# BattMon.net
KiCad netlist of a schematic drawn in EAGLE
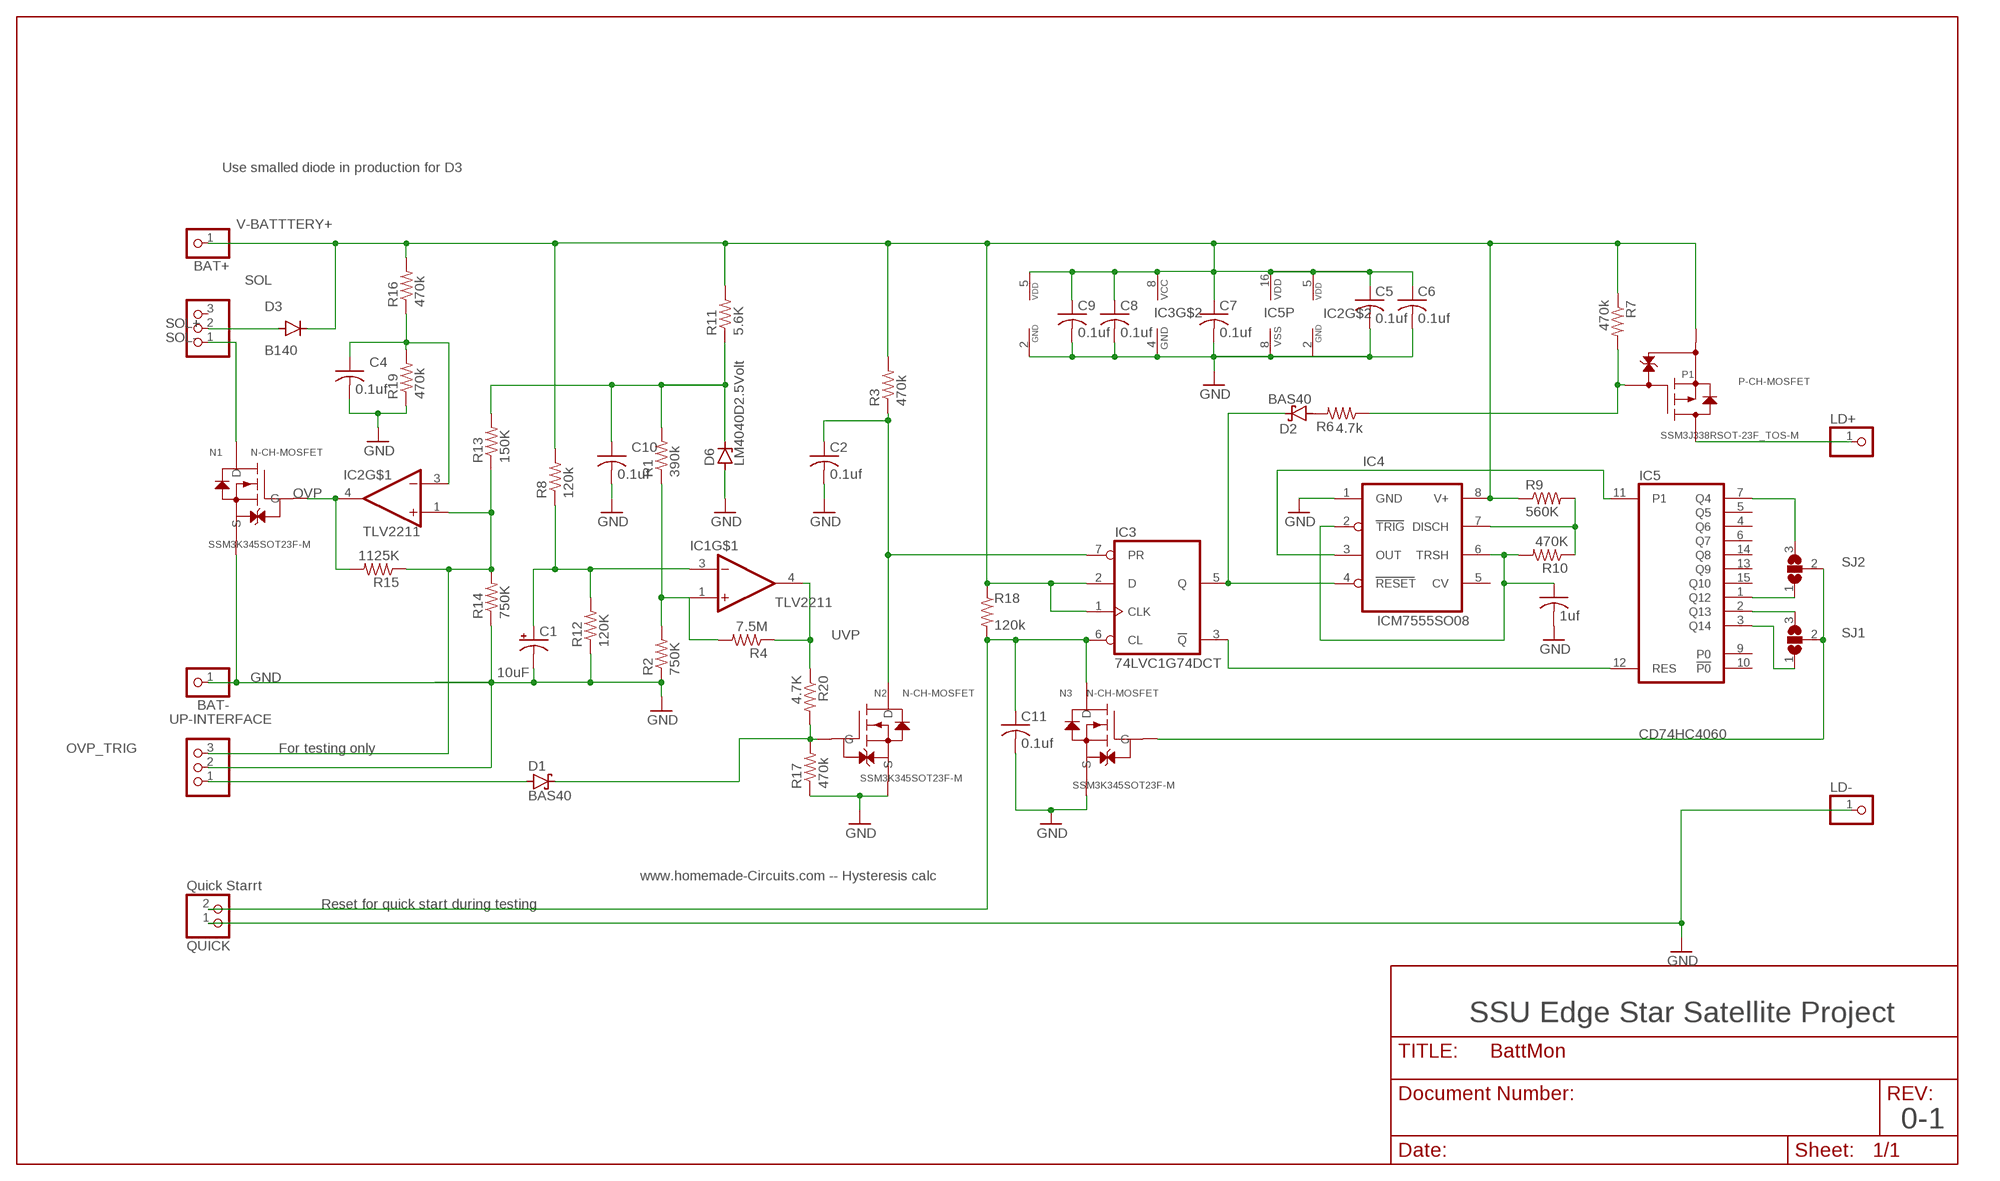
[diagram p0: schematic, sheet 1]

(export (version "E")
  (design (tool "Eeschema 10.0.6"))
  (components
    (comp (ref "BAT+")
      (value "PINHD-1X1")
      (footprint "eagle-import:1X01")
      (libsource (lib "eagle-import") (part "PINHD-1X1"))
    )
    (comp (ref "BAT-")
      (value "PINHD-1X1")
      (footprint "eagle-import:1X01")
      (libsource (lib "eagle-import") (part "PINHD-1X1"))
    )
    (comp (ref "C1")
      (value "10uF")
      (footprint "eagle-import:E2,5-6E")
      (libsource (lib "eagle-import") (part "CPOL-USE2,5-6E"))
    )
    (comp (ref "C2")
      (value "0.1uf")
      (footprint "eagle-import:C0805")
      (libsource (lib "eagle-import") (part "C-USC0805"))
    )
    (comp (ref "C3")
      (value "1uf")
      (footprint "eagle-import:C0805")
      (libsource (lib "eagle-import") (part "C-USC0805"))
    )
    (comp (ref "C4")
      (value "0.1uf")
      (footprint "eagle-import:C0805")
      (libsource (lib "eagle-import") (part "C-USC0805"))
    )
    (comp (ref "C5")
      (value "0.1uf")
      (footprint "eagle-import:C0805")
      (libsource (lib "eagle-import") (part "C-USC0805"))
    )
    (comp (ref "C6")
      (value "0.1uf")
      (footprint "eagle-import:C0805")
      (libsource (lib "eagle-import") (part "C-USC0805"))
    )
    (comp (ref "C7")
      (value "0.1uf")
      (footprint "eagle-import:C0805")
      (libsource (lib "eagle-import") (part "C-USC0805"))
    )
    (comp (ref "C8")
      (value "0.1uf")
      (footprint "eagle-import:C0805")
      (libsource (lib "eagle-import") (part "C-USC0805"))
    )
    (comp (ref "C9")
      (value "0.1uf")
      (footprint "eagle-import:C0805")
      (libsource (lib "eagle-import") (part "C-USC0805"))
    )
    (comp (ref "C10")
      (value "0.1uf")
      (footprint "eagle-import:C0805")
      (libsource (lib "eagle-import") (part "C-USC0805"))
    )
    (comp (ref "C11")
      (value "0.1uf")
      (footprint "eagle-import:C0805")
      (libsource (lib "eagle-import") (part "C-USC0805"))
    )
    (comp (ref "D1")
      (value "BAS40")
      (footprint "eagle-import:SOT23")
      (libsource (lib "eagle-import") (part "BAS40"))
    )
    (comp (ref "D2")
      (value "BAS40")
      (footprint "eagle-import:SOT23")
      (libsource (lib "eagle-import") (part "BAS40"))
    )
    (comp (ref "D3")
      (value "B140")
      (footprint "eagle-import:SMA")
      (libsource (lib "eagle-import") (part "S1M"))
    )
    (comp (ref "D6")
      (value "LM4040D2.5Volt")
      (footprint "eagle-import:SOT23")
      (libsource (lib "eagle-import") (part "LM4040"))
    )
    (comp (ref "IC1")
      (value "TLV2211")
      (footprint "eagle-import:SOT23-5")
      (libsource (lib "eagle-import") (part "TLVB2211"))
    )
    (comp (ref "IC2")
      (value "TLV2211")
      (footprint "eagle-import:SOT23-5")
      (fields (field (name "DIGIKEY") "296-10500-1-ND"))
      (libsource (lib "eagle-import") (part "TLVB2211"))
    )
    (comp (ref "IC3")
      (value "74LVC1G74DCT")
      (footprint "eagle-import:DCT_R-PDSO-G8")
      (fields (field (name "DIGIKEY") "SN74LVC1G74DCTR"))
      (libsource (lib "eagle-import") (part "741G74DCTLVC"))
    )
    (comp (ref "IC4")
      (value "ICM7555SO08")
      (footprint "eagle-import:SO08")
      (libsource (lib "eagle-import") (part "ICM7555SO08"))
    )
    (comp (ref "IC5")
      (value "CD74HC4060")
      (footprint "eagle-import:SO16")
      (fields (field (name "DIGIKEY") "296-25999-1-ND"))
      (libsource (lib "eagle-import") (part "4060D"))
    )
    (comp (ref "LD+")
      (value "PINHD-1X1")
      (footprint "eagle-import:1X01")
      (libsource (lib "eagle-import") (part "PINHD-1X1"))
    )
    (comp (ref "LD-")
      (value "PINHD-1X1")
      (footprint "eagle-import:1X01")
      (libsource (lib "eagle-import") (part "PINHD-1X1"))
    )
    (comp (ref "N1")
      (value "SSM3K345SOT23F-M")
      (footprint "eagle-import:SOT-23F_TOS-M")
      (libsource (lib "eagle-import") (part "SSM3K345SOT23F-M"))
    )
    (comp (ref "N2")
      (value "SSM3K345SOT23F-M")
      (footprint "eagle-import:SOT-23F_TOS-M")
      (libsource (lib "eagle-import") (part "SSM3K345SOT23F-M"))
    )
    (comp (ref "N3")
      (value "SSM3K345SOT23F-M")
      (footprint "eagle-import:SOT-23F_TOS-M")
      (libsource (lib "eagle-import") (part "SSM3K345SOT23F-M"))
    )
    (comp (ref "P1")
      (value "SSM3J338RSOT-23F_TOS-M")
      (footprint "eagle-import:SOT-23F_TOS-M")
      (fields (field (name "MANUFACTURER_PART_NUMBER") "SSM3J338R"))
      (libsource (lib "eagle-import") (part "SSM3J338RSOT-23F_TOS-M"))
    )
    (comp (ref "QUICK")
      (value "Quick Starrt")
      (footprint "eagle-import:1X02")
      (libsource (lib "eagle-import") (part "PINHD-1X2"))
    )
    (comp (ref "R1")
      (value "390k")
      (footprint "eagle-import:R0805")
      (libsource (lib "eagle-import") (part "R-US_R0805"))
    )
    (comp (ref "R2")
      (value "750K")
      (footprint "eagle-import:R0805")
      (libsource (lib "eagle-import") (part "R-US_R0805"))
    )
    (comp (ref "R3")
      (value "470k")
      (footprint "eagle-import:R0805")
      (libsource (lib "eagle-import") (part "R-US_R0805"))
    )
    (comp (ref "R4")
      (value "7.5M")
      (footprint "eagle-import:R0805")
      (libsource (lib "eagle-import") (part "R-US_R0805"))
    )
    (comp (ref "R6")
      (value "4.7k")
      (footprint "eagle-import:R0805")
      (libsource (lib "eagle-import") (part "R-US_R0805"))
    )
    (comp (ref "R7")
      (value "470k")
      (footprint "eagle-import:R0805")
      (libsource (lib "eagle-import") (part "R-US_R0805"))
    )
    (comp (ref "R8")
      (value "120k")
      (footprint "eagle-import:R0805")
      (libsource (lib "eagle-import") (part "R-US_R0805"))
    )
    (comp (ref "R9")
      (value "560K")
      (footprint "eagle-import:R0805")
      (libsource (lib "eagle-import") (part "R-US_R0805"))
    )
    (comp (ref "R10")
      (value "470K")
      (footprint "eagle-import:R0805")
      (libsource (lib "eagle-import") (part "R-US_R0805"))
    )
    (comp (ref "R11")
      (value "5.6K")
      (footprint "eagle-import:R0805")
      (libsource (lib "eagle-import") (part "R-US_R0805"))
    )
    (comp (ref "R12")
      (value "120K")
      (footprint "eagle-import:R0805")
      (libsource (lib "eagle-import") (part "R-US_R0805"))
    )
    (comp (ref "R13")
      (value "150K")
      (footprint "eagle-import:R0805")
      (libsource (lib "eagle-import") (part "R-US_R0805"))
    )
    (comp (ref "R14")
      (value "750K")
      (footprint "eagle-import:R0805")
      (libsource (lib "eagle-import") (part "R-US_R0805"))
    )
    (comp (ref "R15")
      (value "1125K")
      (footprint "eagle-import:R0805")
      (libsource (lib "eagle-import") (part "R-US_R0805"))
    )
    (comp (ref "R16")
      (value "470k")
      (footprint "eagle-import:R0805")
      (libsource (lib "eagle-import") (part "R-US_R0805"))
    )
    (comp (ref "R17")
      (value "470k")
      (footprint "eagle-import:R0805")
      (libsource (lib "eagle-import") (part "R-US_R0805"))
    )
    (comp (ref "R18")
      (value "120k")
      (footprint "eagle-import:R0805")
      (libsource (lib "eagle-import") (part "R-US_R0805"))
    )
    (comp (ref "R19")
      (value "470k")
      (footprint "eagle-import:R0805")
      (libsource (lib "eagle-import") (part "R-US_R0805"))
    )
    (comp (ref "R20")
      (value "4.7K")
      (footprint "eagle-import:R0805")
      (libsource (lib "eagle-import") (part "R-US_R0805"))
    )
    (comp (ref "SJ1")
      (value "SJ2W")
      (footprint "eagle-import:SJ_2")
      (libsource (lib "eagle-import") (part "SJ2W"))
    )
    (comp (ref "SJ2")
      (value "SJ2W")
      (footprint "eagle-import:SJ_2")
      (libsource (lib "eagle-import") (part "SJ2W"))
    )
    (comp (ref "SOL")
      (value "PINHD-1X3")
      (footprint "eagle-import:1X03")
      (libsource (lib "eagle-import") (part "PINHD-1X3"))
    )
    (comp (ref "UP-INTERFACE")
      (value "PINHD-1X3")
      (footprint "eagle-import:1X03")
      (libsource (lib "eagle-import") (part "PINHD-1X3"))
    )
  )
  (nets
    (net (code "1") (name "/OVP") (class "Default")
      (node (ref "IC2") (pin "4") (pinfunction "OUT_4") (pintype "output"))
      (node (ref "N1") (pin "1") (pinfunction "G_1") (pintype "passive"))
      (node (ref "R15") (pin "2") (pinfunction "2_2") (pintype "passive"))
    )
    (net (code "2") (name "/OVP_TRIG") (class "Default")
      (node (ref "IC2") (pin "1") (pinfunction "+IN_1") (pintype "input"))
      (node (ref "R13") (pin "1") (pinfunction "1_1") (pintype "passive"))
      (node (ref "R14") (pin "2") (pinfunction "2_2") (pintype "passive"))
      (node (ref "R15") (pin "1") (pinfunction "1_1") (pintype "passive"))
      (node (ref "UP-INTERFACE") (pin "3") (pinfunction "3_3") (pintype "passive"))
    )
    (net (code "3") (name "/SOL+") (class "Default")
      (node (ref "D3") (pin "A") (pinfunction "A_A") (pintype "passive"))
      (node (ref "SOL") (pin "2") (pinfunction "2_2") (pintype "passive"))
    )
    (net (code "4") (name "/SOL-") (class "Default")
      (node (ref "N1") (pin "3") (pinfunction "D_3") (pintype "passive"))
      (node (ref "SOL") (pin "1") (pinfunction "1_1") (pintype "passive"))
    )
    (net (code "5") (name "/UVP") (class "Default")
      (node (ref "IC1") (pin "4") (pinfunction "OUT_4") (pintype "output"))
      (node (ref "R20") (pin "1") (pinfunction "1_1") (pintype "passive"))
      (node (ref "R4") (pin "1") (pinfunction "1_1") (pintype "passive"))
    )
    (net (code "6") (name "/V-BATTTERY+") (class "Default")
      (node (ref "BAT+") (pin "1") (pinfunction "1_1") (pintype "passive"))
      (node (ref "C5") (pin "1") (pinfunction "1_1") (pintype "passive"))
      (node (ref "C6") (pin "1") (pinfunction "1_1") (pintype "passive"))
      (node (ref "C7") (pin "1") (pinfunction "1_1") (pintype "passive"))
      (node (ref "C8") (pin "1") (pinfunction "1_1") (pintype "passive"))
      (node (ref "C9") (pin "1") (pinfunction "1_1") (pintype "passive"))
      (node (ref "D3") (pin "C") (pinfunction "C_C") (pintype "passive"))
      (node (ref "IC1") (pin "5") (pinfunction "VDD_5") (pintype "power_in"))
      (node (ref "IC2") (pin "5") (pinfunction "VDD_5") (pintype "power_in"))
      (node (ref "IC3") (pin "1") (pinfunction "CLK_1") (pintype "input"))
      (node (ref "IC3") (pin "2") (pinfunction "D_2") (pintype "input"))
      (node (ref "IC3") (pin "8") (pinfunction "VCC_8") (pintype "power_in"))
      (node (ref "IC4") (pin "8") (pinfunction "V+_8") (pintype "power_in"))
      (node (ref "IC5") (pin "16") (pinfunction "VDD_16") (pintype "power_in"))
      (node (ref "P1") (pin "2") (pinfunction "2_2") (pintype "passive"))
      (node (ref "R11") (pin "2") (pinfunction "2_2") (pintype "passive"))
      (node (ref "R16") (pin "2") (pinfunction "2_2") (pintype "passive"))
      (node (ref "R18") (pin "1") (pinfunction "1_1") (pintype "passive"))
      (node (ref "R3") (pin "2") (pinfunction "2_2") (pintype "passive"))
      (node (ref "R7") (pin "1") (pinfunction "1_1") (pintype "passive"))
      (node (ref "R8") (pin "2") (pinfunction "2_2") (pintype "passive"))
      (node (ref "R9") (pin "1") (pinfunction "1_1") (pintype "passive"))
    )
    (net (code "7") (name "GND") (class "Default")
      (node (ref "BAT-") (pin "1") (pinfunction "1_1") (pintype "passive"))
      (node (ref "C1") (pin "-") (pinfunction "-_-") (pintype "passive"))
      (node (ref "C10") (pin "2") (pinfunction "2_2") (pintype "passive"))
      (node (ref "C11") (pin "2") (pinfunction "2_2") (pintype "passive"))
      (node (ref "C2") (pin "2") (pinfunction "2_2") (pintype "passive"))
      (node (ref "C3") (pin "2") (pinfunction "2_2") (pintype "passive"))
      (node (ref "C4") (pin "2") (pinfunction "2_2") (pintype "passive"))
      (node (ref "C5") (pin "2") (pinfunction "2_2") (pintype "passive"))
      (node (ref "C6") (pin "2") (pinfunction "2_2") (pintype "passive"))
      (node (ref "C7") (pin "2") (pinfunction "2_2") (pintype "passive"))
      (node (ref "C8") (pin "2") (pinfunction "2_2") (pintype "passive"))
      (node (ref "C9") (pin "2") (pinfunction "2_2") (pintype "passive"))
      (node (ref "D6") (pin "2") (pinfunction "A_2") (pintype "passive"))
      (node (ref "IC1") (pin "2") (pinfunction "VDD_GND_2") (pintype "power_in"))
      (node (ref "IC2") (pin "2") (pinfunction "VDD_GND_2") (pintype "power_in"))
      (node (ref "IC3") (pin "4") (pinfunction "GND_4") (pintype "power_in"))
      (node (ref "IC4") (pin "1") (pinfunction "GND_1") (pintype "power_in"))
      (node (ref "IC5") (pin "8") (pinfunction "VSS_8") (pintype "power_in"))
      (node (ref "LD-") (pin "1") (pinfunction "1_1") (pintype "passive"))
      (node (ref "N1") (pin "2") (pinfunction "S_2") (pintype "passive"))
      (node (ref "N2") (pin "2") (pinfunction "S_2") (pintype "passive"))
      (node (ref "N3") (pin "2") (pinfunction "S_2") (pintype "passive"))
      (node (ref "QUICK") (pin "1") (pinfunction "1_1") (pintype "passive"))
      (node (ref "R12") (pin "1") (pinfunction "1_1") (pintype "passive"))
      (node (ref "R14") (pin "1") (pinfunction "1_1") (pintype "passive"))
      (node (ref "R17") (pin "1") (pinfunction "1_1") (pintype "passive"))
      (node (ref "R19") (pin "1") (pinfunction "1_1") (pintype "passive"))
      (node (ref "R2") (pin "1") (pinfunction "1_1") (pintype "passive"))
      (node (ref "UP-INTERFACE") (pin "2") (pinfunction "2_2") (pintype "passive"))
    )
    (net (code "8") (name "Net-(D1-A)") (class "Default")
      (node (ref "D1") (pin "1") (pinfunction "A_1") (pintype "passive"))
      (node (ref "UP-INTERFACE") (pin "1") (pinfunction "1_1") (pintype "passive"))
    )
    (net (code "9") (name "Net-(D1-C)") (class "Default")
      (node (ref "D1") (pin "3") (pinfunction "C_3") (pintype "passive"))
      (node (ref "N2") (pin "1") (pinfunction "G_1") (pintype "passive"))
      (node (ref "R17") (pin "2") (pinfunction "2_2") (pintype "passive"))
      (node (ref "R20") (pin "2") (pinfunction "2_2") (pintype "passive"))
    )
    (net (code "10") (name "Net-(D2-A)") (class "Default")
      (node (ref "D2") (pin "1") (pinfunction "A_1") (pintype "passive"))
      (node (ref "R6") (pin "2") (pinfunction "2_2") (pintype "passive"))
    )
    (net (code "11") (name "Net-(D2-C)") (class "Default")
      (node (ref "D2") (pin "3") (pinfunction "C_3") (pintype "passive"))
      (node (ref "IC3") (pin "5") (pinfunction "Q_5") (pintype "output"))
      (node (ref "IC4") (pin "4") (pinfunction "RESET_4") (pintype "input"))
    )
    (net (code "12") (name "Net-(D6-C)") (class "Default")
      (node (ref "C10") (pin "1") (pinfunction "1_1") (pintype "passive"))
      (node (ref "D6") (pin "1") (pinfunction "C_1") (pintype "passive"))
      (node (ref "R1") (pin "2") (pinfunction "2_2") (pintype "passive"))
      (node (ref "R11") (pin "1") (pinfunction "1_1") (pintype "passive"))
      (node (ref "R13") (pin "2") (pinfunction "2_2") (pintype "passive"))
    )
    (net (code "13") (name "Net-(IC1A-+IN)") (class "Default")
      (node (ref "IC1") (pin "1") (pinfunction "+IN_1") (pintype "input"))
      (node (ref "R1") (pin "1") (pinfunction "1_1") (pintype "passive"))
      (node (ref "R2") (pin "2") (pinfunction "2_2") (pintype "passive"))
      (node (ref "R4") (pin "2") (pinfunction "2_2") (pintype "passive"))
    )
    (net (code "14") (name "Net-(IC1A--IN)") (class "Default")
      (node (ref "C1") (pin "+") (pinfunction "+_+") (pintype "passive"))
      (node (ref "IC1") (pin "3") (pinfunction "-IN_3") (pintype "input"))
      (node (ref "R12") (pin "2") (pinfunction "2_2") (pintype "passive"))
      (node (ref "R8") (pin "1") (pinfunction "1_1") (pintype "passive"))
    )
    (net (code "15") (name "Net-(IC2A--IN)") (class "Default")
      (node (ref "C4") (pin "1") (pinfunction "1_1") (pintype "passive"))
      (node (ref "IC2") (pin "3") (pinfunction "-IN_3") (pintype "input"))
      (node (ref "R16") (pin "1") (pinfunction "1_1") (pintype "passive"))
      (node (ref "R19") (pin "2") (pinfunction "2_2") (pintype "passive"))
    )
    (net (code "16") (name "Net-(IC3A-CL)") (class "Default")
      (node (ref "C11") (pin "1") (pinfunction "1_1") (pintype "passive"))
      (node (ref "IC3") (pin "6") (pinfunction "CL_6") (pintype "input"))
      (node (ref "N3") (pin "3") (pinfunction "D_3") (pintype "passive"))
      (node (ref "QUICK") (pin "2") (pinfunction "2_2") (pintype "passive"))
      (node (ref "R18") (pin "2") (pinfunction "2_2") (pintype "passive"))
    )
    (net (code "17") (name "Net-(IC3A-PR)") (class "Default")
      (node (ref "C2") (pin "1") (pinfunction "1_1") (pintype "passive"))
      (node (ref "IC3") (pin "7") (pinfunction "PR_7") (pintype "input"))
      (node (ref "N2") (pin "3") (pinfunction "D_3") (pintype "passive"))
      (node (ref "R3") (pin "1") (pinfunction "1_1") (pintype "passive"))
    )
    (net (code "18") (name "Net-(IC3A-~{Q})") (class "Default")
      (node (ref "IC3") (pin "3") (pinfunction "~{Q}_3") (pintype "output"))
      (node (ref "IC5") (pin "12") (pinfunction "RES_12") (pintype "input"))
    )
    (net (code "19") (name "Net-(IC4-DISCH)") (class "Default")
      (node (ref "IC4") (pin "7") (pinfunction "DISCH_7") (pintype "input"))
      (node (ref "R10") (pin "1") (pinfunction "1_1") (pintype "passive"))
      (node (ref "R9") (pin "2") (pinfunction "2_2") (pintype "passive"))
    )
    (net (code "20") (name "Net-(IC4-OUT)") (class "Default")
      (node (ref "IC4") (pin "3") (pinfunction "OUT_3") (pintype "output"))
      (node (ref "IC5") (pin "11") (pinfunction "P1_11") (pintype "input"))
    )
    (net (code "21") (name "Net-(IC4-TRIG)") (class "Default")
      (node (ref "C3") (pin "1") (pinfunction "1_1") (pintype "passive"))
      (node (ref "IC4") (pin "2") (pinfunction "TRIG_2") (pintype "bidirectional"))
      (node (ref "IC4") (pin "6") (pinfunction "TRSH_6") (pintype "input"))
      (node (ref "R10") (pin "2") (pinfunction "2_2") (pintype "passive"))
    )
    (net (code "22") (name "Net-(IC5A-Q4)") (class "Default")
      (node (ref "IC5") (pin "7") (pinfunction "Q4_7") (pintype "output"))
      (node (ref "SJ2") (pin "3") (pinfunction "3_3") (pintype "passive"))
    )
    (net (code "23") (name "Net-(IC5A-Q12)") (class "Default")
      (node (ref "IC5") (pin "1") (pinfunction "Q12_1") (pintype "output"))
      (node (ref "SJ2") (pin "1") (pinfunction "1_1") (pintype "passive"))
    )
    (net (code "24") (name "Net-(IC5A-Q13)") (class "Default")
      (node (ref "IC5") (pin "2") (pinfunction "Q13_2") (pintype "output"))
      (node (ref "SJ1") (pin "3") (pinfunction "3_3") (pintype "passive"))
    )
    (net (code "25") (name "Net-(IC5A-Q14)") (class "Default")
      (node (ref "IC5") (pin "3") (pinfunction "Q14_3") (pintype "output"))
      (node (ref "SJ1") (pin "1") (pinfunction "1_1") (pintype "passive"))
    )
    (net (code "26") (name "Net-(LD+-Pad1)") (class "Default")
      (node (ref "LD+") (pin "1") (pinfunction "1_1") (pintype "passive"))
      (node (ref "P1") (pin "3") (pinfunction "3_3") (pintype "passive"))
    )
    (net (code "27") (name "Net-(N3-G)") (class "Default")
      (node (ref "N3") (pin "1") (pinfunction "G_1") (pintype "passive"))
      (node (ref "SJ1") (pin "2") (pinfunction "2_2") (pintype "passive"))
      (node (ref "SJ2") (pin "2") (pinfunction "2_2") (pintype "passive"))
    )
    (net (code "28") (name "Net-(P1-Pad1)") (class "Default")
      (node (ref "P1") (pin "1") (pinfunction "1_1") (pintype "passive"))
      (node (ref "R6") (pin "1") (pinfunction "1_1") (pintype "passive"))
      (node (ref "R7") (pin "2") (pinfunction "2_2") (pintype "passive"))
    )
    (net (code "29") (name "unconnected-(IC4-CV-Pad5)") (class "Default")
      (node (ref "IC4") (pin "5") (pinfunction "CV_5") (pintype "passive"))
    )
    (net (code "30") (name "unconnected-(IC5A-P0-Pad9)") (class "Default")
      (node (ref "IC5") (pin "9") (pinfunction "P0_9") (pintype "output"))
    )
    (net (code "31") (name "unconnected-(IC5A-Q5-Pad5)") (class "Default")
      (node (ref "IC5") (pin "5") (pinfunction "Q5_5") (pintype "output"))
    )
    (net (code "32") (name "unconnected-(IC5A-Q6-Pad4)") (class "Default")
      (node (ref "IC5") (pin "4") (pinfunction "Q6_4") (pintype "output"))
    )
    (net (code "33") (name "unconnected-(IC5A-Q7-Pad6)") (class "Default")
      (node (ref "IC5") (pin "6") (pinfunction "Q7_6") (pintype "output"))
    )
    (net (code "34") (name "unconnected-(IC5A-Q8-Pad14)") (class "Default")
      (node (ref "IC5") (pin "14") (pinfunction "Q8_14") (pintype "output"))
    )
    (net (code "35") (name "unconnected-(IC5A-Q9-Pad13)") (class "Default")
      (node (ref "IC5") (pin "13") (pinfunction "Q9_13") (pintype "output"))
    )
    (net (code "36") (name "unconnected-(IC5A-Q10-Pad15)") (class "Default")
      (node (ref "IC5") (pin "15") (pinfunction "Q10_15") (pintype "output"))
    )
    (net (code "37") (name "unconnected-(IC5A-~{P0}-Pad10)") (class "Default")
      (node (ref "IC5") (pin "10") (pinfunction "~{P0}_10") (pintype "output"))
    )
    (net (code "38") (name "unconnected-(SOL-Pad3)") (class "Default")
      (node (ref "SOL") (pin "3") (pinfunction "3_3") (pintype "passive"))
    )
  )
)
